# ESP32_USBC.net
KiCad netlist of a schematic drawn in Altium Designer
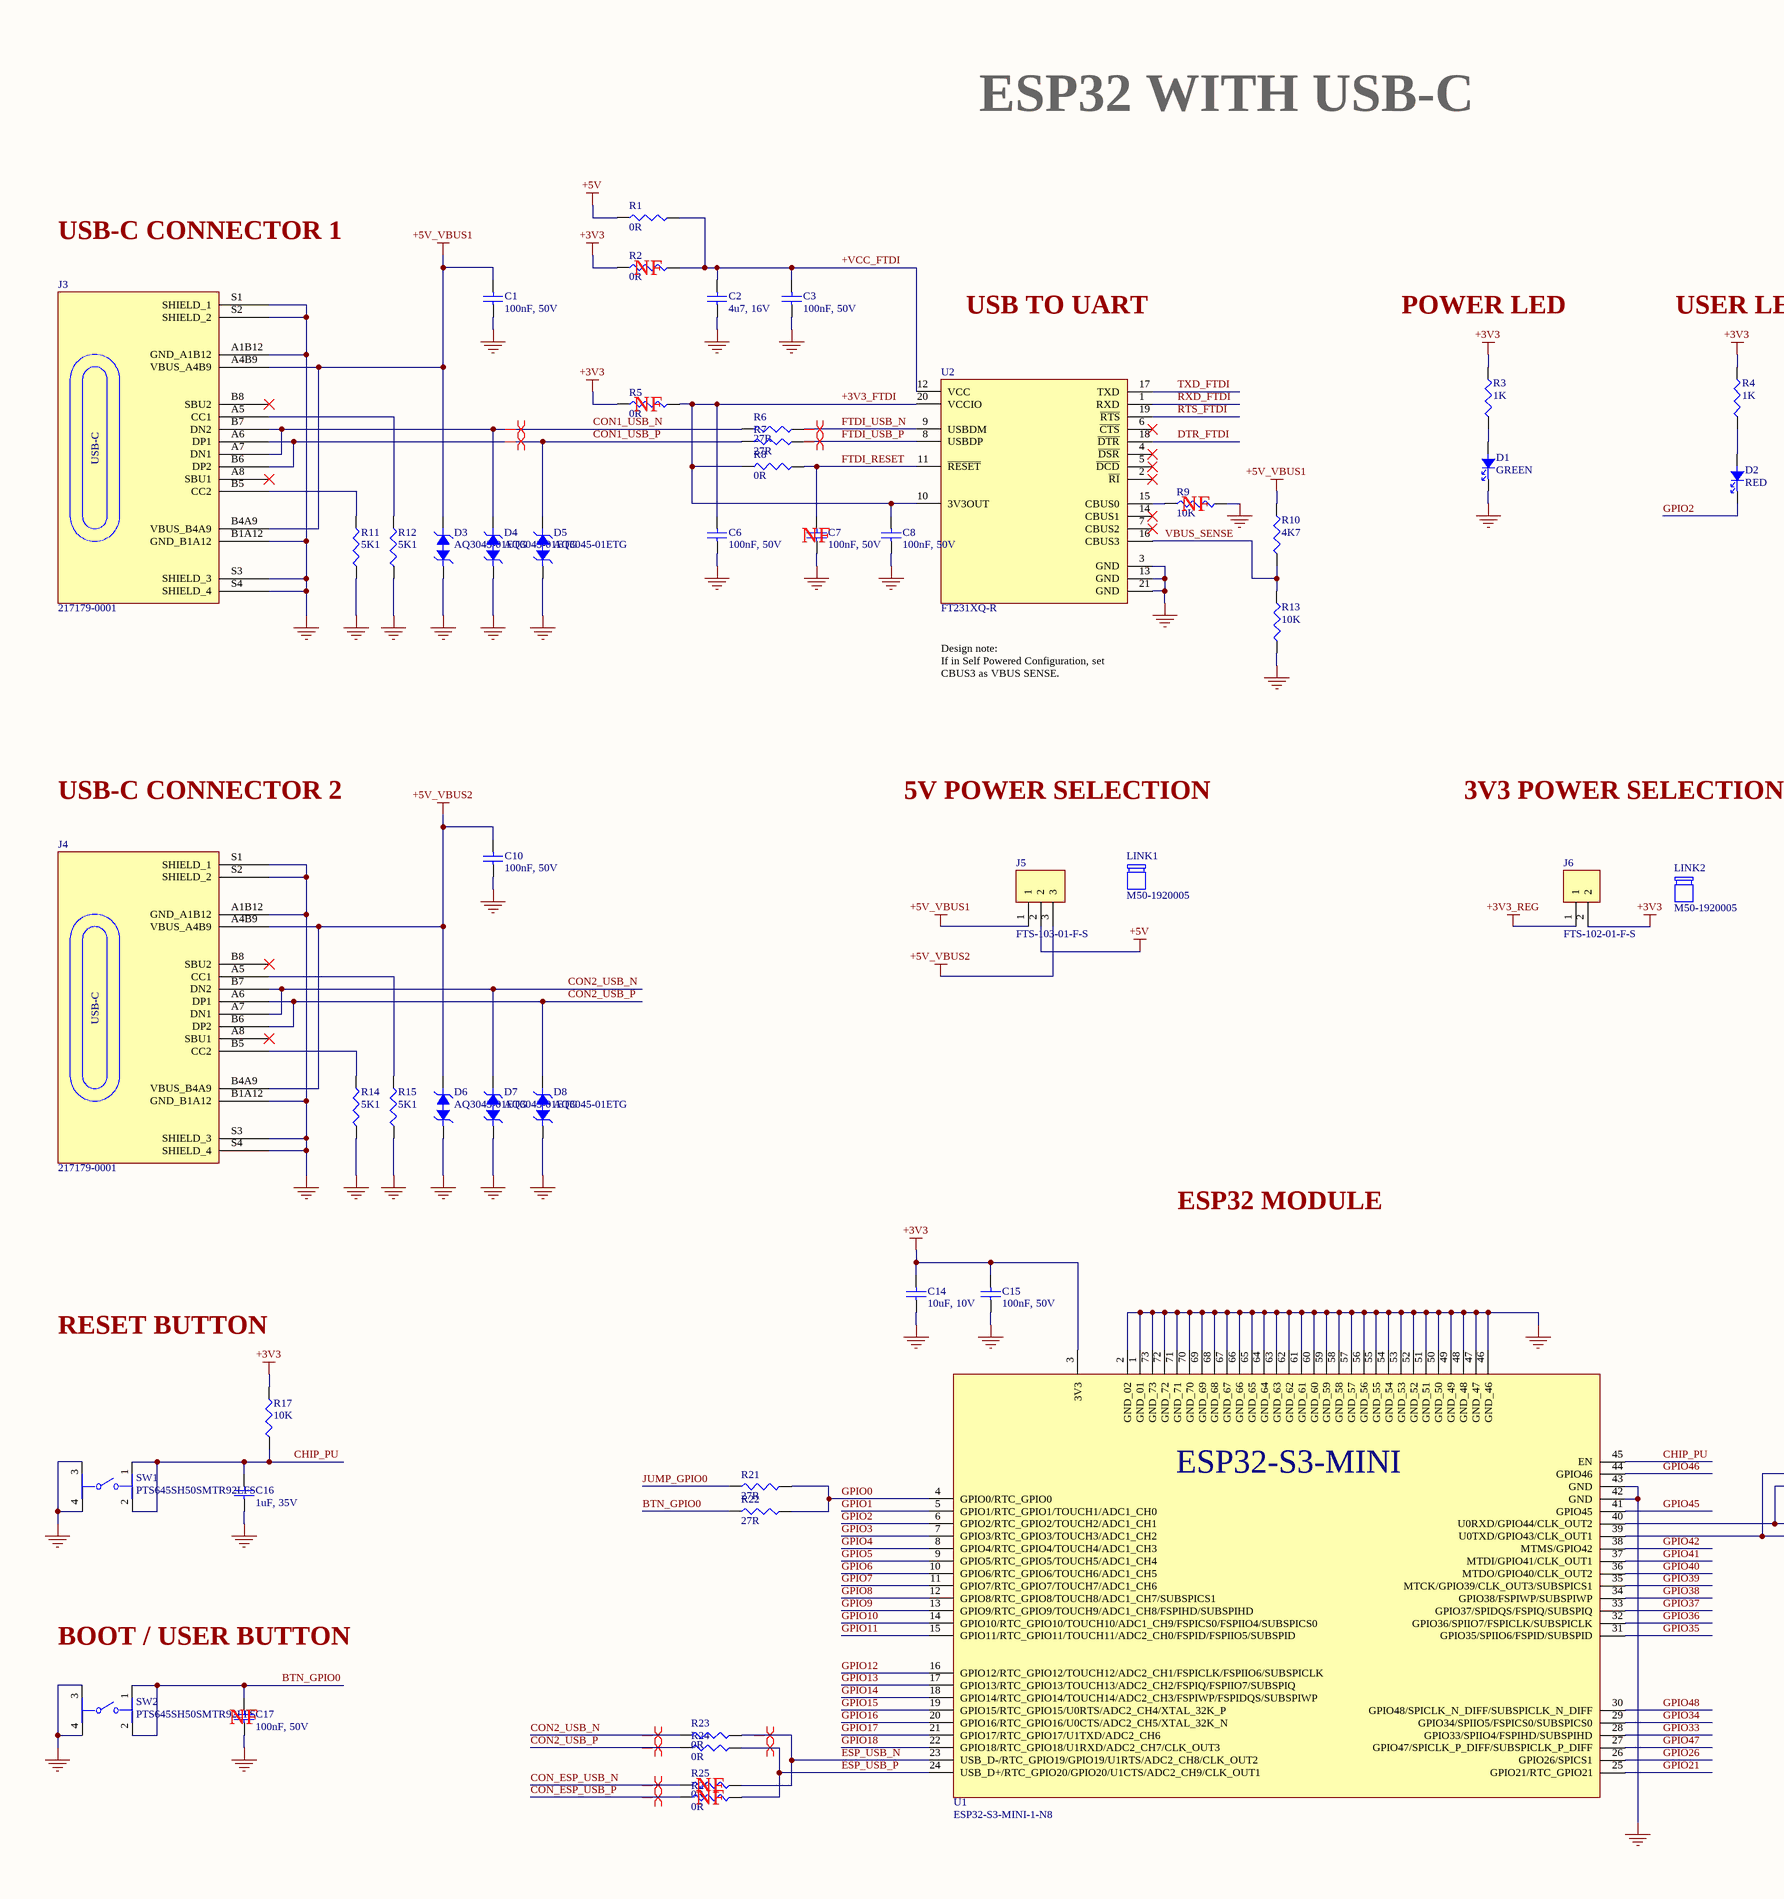
[diagram p0: ESP32_USBC.SchDoc, left]
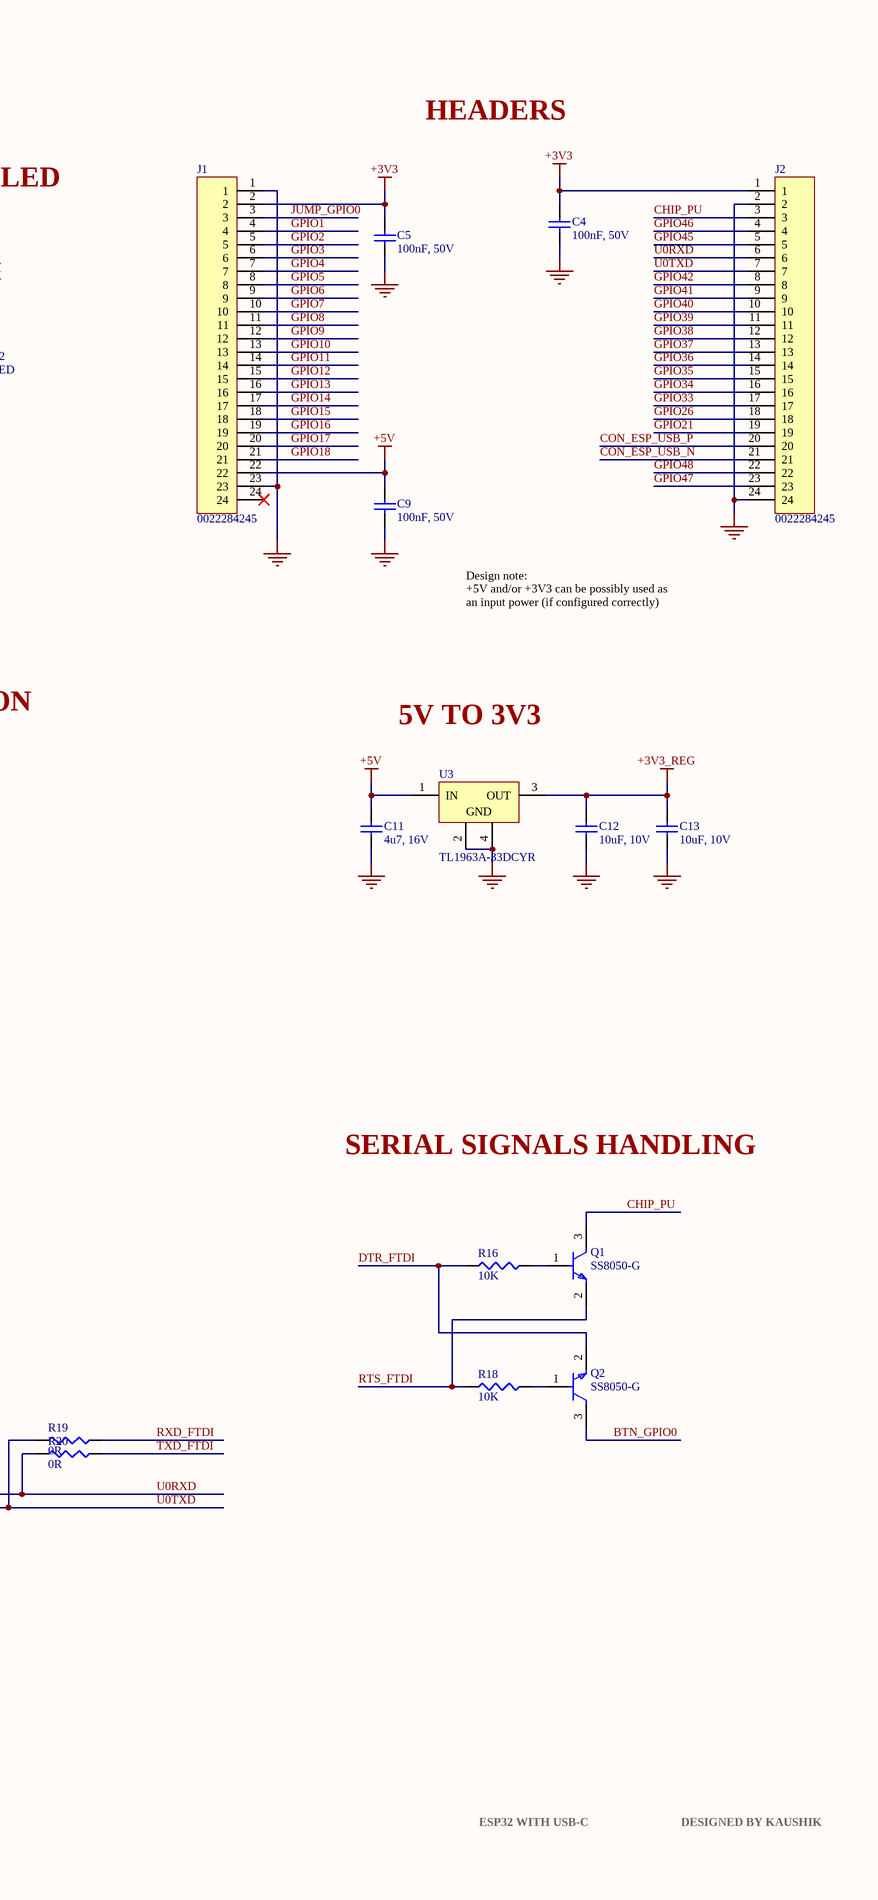
[diagram p1: ESP32_USBC.SchDoc, right]

(export (version "E")
  (design (tool "Eeschema 10.0.6"))
  (components
    (comp (ref "C1")
      (value "100nF, 50V")
      (footprint "CAPC1005X55N")
      (description "CAP CER 0.1UF 50V X7R 0402")
      (fields
        (field (name "MANUFACTURER") "Samsung")
        (field (name "MANUFACTURER PART NUMBER") "CL05B104KB54PNC")
      )
      (libsource (lib "Schlib") (part "CL05B104KB54PNC"))
    )
    (comp (ref "C2")
      (value "4u7, 16V")
      (footprint "CAPC1005X55N")
      (description "CAP CER 4.7UF 16V X5R 0402")
      (fields
        (field (name "MANUFACTURER") "Samsung")
        (field (name "MANUFACTURER PART NUMBER") "CL05A475MO5NUNC")
      )
      (libsource (lib "Schlib") (part "CL05A475MO5NUNC"))
    )
    (comp (ref "C3")
      (value "100nF, 50V")
      (footprint "CAPC1005X55N")
      (description "CAP CER 0.1UF 50V X7R 0402")
      (fields
        (field (name "MANUFACTURER") "Samsung")
        (field (name "MANUFACTURER PART NUMBER") "CL05B104KB54PNC")
      )
      (libsource (lib "Schlib") (part "CL05B104KB54PNC"))
    )
    (comp (ref "C4")
      (value "100nF, 50V")
      (footprint "CAPC1005X55N")
      (description "CAP CER 0.1UF 50V X7R 0402")
      (fields
        (field (name "MANUFACTURER") "Samsung")
        (field (name "MANUFACTURER PART NUMBER") "CL05B104KB54PNC")
      )
      (libsource (lib "Schlib") (part "CL05B104KB54PNC"))
    )
    (comp (ref "C5")
      (value "100nF, 50V")
      (footprint "CAPC1005X55N")
      (description "CAP CER 0.1UF 50V X7R 0402")
      (fields
        (field (name "MANUFACTURER") "Samsung")
        (field (name "MANUFACTURER PART NUMBER") "CL05B104KB54PNC")
      )
      (libsource (lib "Schlib") (part "CL05B104KB54PNC"))
    )
    (comp (ref "C6")
      (value "100nF, 50V")
      (footprint "CAPC1005X55N")
      (description "CAP CER 0.1UF 50V X7R 0402")
      (fields
        (field (name "MANUFACTURER") "Samsung")
        (field (name "MANUFACTURER PART NUMBER") "CL05B104KB54PNC")
      )
      (libsource (lib "Schlib") (part "CL05B104KB54PNC"))
    )
    (comp (ref "C7")
      (value "100nF, 50V")
      (footprint "CAPC1005X55N")
      (description "CAP CER 0.1UF 50V X7R 0402")
      (fields
        (field (name "MANUFACTURER") "Samsung")
        (field (name "MANUFACTURER PART NUMBER") "CL05B104KB54PNC")
      )
      (libsource (lib "Schlib") (part "CL05B104KB54PNC"))
    )
    (comp (ref "C8")
      (value "100nF, 50V")
      (footprint "CAPC1005X55N")
      (description "CAP CER 0.1UF 50V X7R 0402")
      (fields
        (field (name "MANUFACTURER") "Samsung")
        (field (name "MANUFACTURER PART NUMBER") "CL05B104KB54PNC")
      )
      (libsource (lib "Schlib") (part "CL05B104KB54PNC"))
    )
    (comp (ref "C9")
      (value "100nF, 50V")
      (footprint "CAPC1005X55N")
      (description "CAP CER 0.1UF 50V X7R 0402")
      (fields
        (field (name "MANUFACTURER") "Samsung")
        (field (name "MANUFACTURER PART NUMBER") "CL05B104KB54PNC")
      )
      (libsource (lib "Schlib") (part "CL05B104KB54PNC"))
    )
    (comp (ref "C10")
      (value "100nF, 50V")
      (footprint "CAPC1005X55N")
      (description "CAP CER 0.1UF 50V X7R 0402")
      (fields
        (field (name "MANUFACTURER") "Samsung")
        (field (name "MANUFACTURER PART NUMBER") "CL05B104KB54PNC")
      )
      (libsource (lib "Schlib") (part "CL05B104KB54PNC"))
    )
    (comp (ref "C11")
      (value "4u7, 16V")
      (footprint "CAPC1005X55N")
      (description "CAP CER 4.7UF 16V X5R 0402")
      (fields
        (field (name "MANUFACTURER") "Samsung")
        (field (name "MANUFACTURER PART NUMBER") "CL05A475MO5NUNC")
      )
      (libsource (lib "Schlib") (part "CL05A475MO5NUNC"))
    )
    (comp (ref "C12")
      (value "10uF, 10V")
      (footprint "CAPC1005X55N")
      (description "CAP CER 10UF 10V X5R 0402")
      (fields
        (field (name "MANUFACTURER") "Samsung")
        (field (name "MANUFACTURER PART NUMBER") "CL05A106MP8NUB8")
      )
      (libsource (lib "Schlib") (part "CL05A106MP8NUB8"))
    )
    (comp (ref "C13")
      (value "10uF, 10V")
      (footprint "CAPC1005X55N")
      (description "CAP CER 10UF 10V X5R 0402")
      (fields
        (field (name "MANUFACTURER") "Samsung")
        (field (name "MANUFACTURER PART NUMBER") "CL05A106MP8NUB8")
      )
      (libsource (lib "Schlib") (part "CL05A106MP8NUB8"))
    )
    (comp (ref "C14")
      (value "10uF, 10V")
      (footprint "CAPC1005X55N")
      (description "CAP CER 10UF 10V X5R 0402")
      (fields
        (field (name "MANUFACTURER") "Samsung")
        (field (name "MANUFACTURER PART NUMBER") "CL05A106MP8NUB8")
      )
      (libsource (lib "Schlib") (part "CL05A106MP8NUB8"))
    )
    (comp (ref "C15")
      (value "100nF, 50V")
      (footprint "CAPC1005X55N")
      (description "CAP CER 0.1UF 50V X7R 0402")
      (fields
        (field (name "MANUFACTURER") "Samsung")
        (field (name "MANUFACTURER PART NUMBER") "CL05B104KB54PNC")
      )
      (libsource (lib "Schlib") (part "CL05B104KB54PNC"))
    )
    (comp (ref "C16")
      (value "1uF, 35V")
      (footprint "CAPC1005X55N")
      (description "CAP CER 1UF 35V X5R 0402")
      (fields
        (field (name "MANUFACTURER") "Samsung")
        (field (name "MANUFACTURER PART NUMBER") "CL05A105KL5NRNC")
      )
      (libsource (lib "Schlib") (part "CL05A105KL5NRNC"))
    )
    (comp (ref "C17")
      (value "100nF, 50V")
      (footprint "CAPC1005X55N")
      (description "CAP CER 0.1UF 50V X7R 0402")
      (fields
        (field (name "MANUFACTURER") "Samsung")
        (field (name "MANUFACTURER PART NUMBER") "CL05B104KB54PNC")
      )
      (libsource (lib "Schlib") (part "CL05B104KB54PNC"))
    )
    (comp (ref "D1")
      (value "GREEN")
      (footprint "LED0402G")
      (description "LED YLW-GRN 0402 SMD")
      (fields
        (field (name "MANUFACTURER") "Vishay")
        (field (name "MANUFACTURER PART NUMBER") "VLMG1500-GS08")
      )
      (libsource (lib "Schlib") (part "VLMG1500-GS08"))
    )
    (comp (ref "D2")
      (value "RED")
      (footprint "LED0402R")
      (description "LED RED 0402 SMD")
      (fields
        (field (name "MANUFACTURER") "Vishay")
        (field (name "MANUFACTURER PART NUMBER") "VLMS1500-GS08")
      )
      (libsource (lib "Schlib") (part "VLMS1500-GS08"))
    )
    (comp (ref "D3")
      (value "AQ3045-01ETG")
      (footprint "SOD882")
      (description "TVS DIODE 5.3VWM 12VC SOD882")
      (fields (field (name "MANUFACTURER") "Littelfuse") (field (name "LCSC PART NUMBER") "C3710326"))
      (libsource (lib "Schlib") (part "AQ3045-01ETG"))
    )
    (comp (ref "D4")
      (value "AQ3045-01ETG")
      (footprint "SOD882")
      (description "TVS DIODE 5.3VWM 12VC SOD882")
      (fields (field (name "MANUFACTURER") "Littelfuse") (field (name "LCSC PART NUMBER") "C3710326"))
      (libsource (lib "Schlib") (part "AQ3045-01ETG"))
    )
    (comp (ref "D5")
      (value "AQ3045-01ETG")
      (footprint "SOD882")
      (description "TVS DIODE 5.3VWM 12VC SOD882")
      (fields (field (name "MANUFACTURER") "Littelfuse") (field (name "LCSC PART NUMBER") "C3710326"))
      (libsource (lib "Schlib") (part "AQ3045-01ETG"))
    )
    (comp (ref "D6")
      (value "AQ3045-01ETG")
      (footprint "SOD882")
      (description "TVS DIODE 5.3VWM 12VC SOD882")
      (fields (field (name "MANUFACTURER") "Littelfuse") (field (name "LCSC PART NUMBER") "C3710326"))
      (libsource (lib "Schlib") (part "AQ3045-01ETG"))
    )
    (comp (ref "D7")
      (value "AQ3045-01ETG")
      (footprint "SOD882")
      (description "TVS DIODE 5.3VWM 12VC SOD882")
      (fields (field (name "MANUFACTURER") "Littelfuse") (field (name "LCSC PART NUMBER") "C3710326"))
      (libsource (lib "Schlib") (part "AQ3045-01ETG"))
    )
    (comp (ref "D8")
      (value "AQ3045-01ETG")
      (footprint "SOD882")
      (description "TVS DIODE 5.3VWM 12VC SOD882")
      (fields (field (name "MANUFACTURER") "Littelfuse") (field (name "LCSC PART NUMBER") "C3710326"))
      (libsource (lib "Schlib") (part "AQ3045-01ETG"))
    )
    (comp (ref "J1")
      (value "0022284245")
      (footprint "HDR_1X24_2.54MM")
      (description "CONN HEADER VERT 24POS 2.54MM")
      (fields (field (name "MANUFACTURER") "Molex") (field (name "LCSC PART NUMBER") "C7145888"))
      (libsource (lib "Schlib") (part "0022284245"))
    )
    (comp (ref "J2")
      (value "0022284245")
      (footprint "HDR_1X24_2.54MM")
      (description "CONN HEADER VERT 24POS 2.54MM")
      (fields (field (name "MANUFACTURER") "Molex") (field (name "LCSC PART NUMBER") "C7145888"))
      (libsource (lib "") (part "0022284245_1"))
    )
    (comp (ref "J3")
      (value "217179-0001")
      (footprint "FP-2171790001-MFG")
      (description "CONN RCP USB2.0 TYP C 24P SMD RA")
      (fields (field (name "MANUFACTURER") "Molex") (field (name "LCSC PART NUMBER") "C3197684"))
      (libsource (lib "Schlib") (part "217179-0001"))
    )
    (comp (ref "J4")
      (value "217179-0001")
      (footprint "FP-2171790001-MFG")
      (description "CONN RCP USB2.0 TYP C 24P SMD RA")
      (fields (field (name "MANUFACTURER") "Molex") (field (name "LCSC PART NUMBER") "C3197684"))
      (libsource (lib "Schlib") (part "217179-0001"))
    )
    (comp (ref "J5")
      (value "FTS-103-01-F-S")
      (footprint "HDR_1X3_1.27MM")
      (description "CONN HEADER VERT 3POS 1.27MM")
      (fields (field (name "MANUFACTURER") "Samtec") (field (name "LCSC PART NUMBER") "C3333578"))
      (libsource (lib "Schlib") (part "FTS-103-01-F-S"))
    )
    (comp (ref "J6")
      (value "FTS-102-01-F-S")
      (footprint "HDR_1X2_1.27MM")
      (description "CONN HEADER VERT 2POS 1.27MM")
      (fields (field (name "MANUFACTURER") "Samtec") (field (name "LCSC PART NUMBER") "C6045317"))
      (libsource (lib "Schlib") (part "FTS-102-01-F-S"))
    )
    (comp (ref "LINK1")
      (value "M50-1920005")
      (description "CONN SHUNT 1.27MM RED")
      (fields (field (name "MANUFACTURER") "Harwin") (field (name "LCSC PART NUMBER") "C6985646"))
      (libsource (lib "Schlib") (part "M50-1920005"))
    )
    (comp (ref "LINK2")
      (value "M50-1920005")
      (description "CONN SHUNT 1.27MM RED")
      (fields (field (name "MANUFACTURER") "Harwin") (field (name "LCSC PART NUMBER") "C6985646"))
      (libsource (lib "Schlib") (part "M50-1920005"))
    )
    (comp (ref "Q1")
      (value "SS8050-G")
      (footprint "FP-SS8050-G-IPC_B")
      (description "TRANS NPN 25V 1.5A SOT23-3")
      (fields (field (name "MANUFACTURER") "Comchip") (field (name "LCSC PART NUMBER") "C164886"))
      (libsource (lib "Schlib") (part "SS8050-G"))
    )
    (comp (ref "Q2")
      (value "SS8050-G")
      (footprint "FP-SS8050-G-IPC_B")
      (description "TRANS NPN 25V 1.5A SOT23-3")
      (fields (field (name "MANUFACTURER") "Comchip") (field (name "LCSC PART NUMBER") "C164886"))
      (libsource (lib "Schlib") (part "SS8050-G"))
    )
    (comp (ref "R1")
      (value "0R")
      (footprint "RESC1005X37N")
      (description "RES 0 OHM JUMPER 1/16W 0402")
      (fields
        (field (name "MANUFACTURER") "Yageo")
        (field (name "MANUFACTURER PART NUMBER") "RC0402JR-070RL")
      )
      (libsource (lib "Schlib") (part "RC0402JR-070RL"))
    )
    (comp (ref "R2")
      (value "0R")
      (footprint "RESC1005X37N")
      (description "RES 0 OHM JUMPER 1/16W 0402")
      (fields
        (field (name "MANUFACTURER") "Yageo")
        (field (name "MANUFACTURER PART NUMBER") "RC0402JR-070RL")
      )
      (libsource (lib "Schlib") (part "RC0402JR-070RL"))
    )
    (comp (ref "R3")
      (value "1K")
      (footprint "RESC1005X37N")
      (description "RES 1K OHM 1% 1/16W 0402")
      (fields
        (field (name "MANUFACTURER") "Yageo")
        (field (name "MANUFACTURER PART NUMBER") "RC0402FR-071KL")
      )
      (libsource (lib "Schlib") (part "RC0402FR-071KL"))
    )
    (comp (ref "R4")
      (value "1K")
      (footprint "RESC1005X37N")
      (description "RES 1K OHM 1% 1/16W 0402")
      (fields
        (field (name "MANUFACTURER") "Yageo")
        (field (name "MANUFACTURER PART NUMBER") "RC0402FR-071KL")
      )
      (libsource (lib "Schlib") (part "RC0402FR-071KL"))
    )
    (comp (ref "R5")
      (value "0R")
      (footprint "RESC1005X37N")
      (description "RES 0 OHM JUMPER 1/16W 0402")
      (fields
        (field (name "MANUFACTURER") "Yageo")
        (field (name "MANUFACTURER PART NUMBER") "RC0402JR-070RL")
      )
      (libsource (lib "Schlib") (part "RC0402JR-070RL"))
    )
    (comp (ref "R6")
      (value "27R")
      (footprint "RESC1005X37N")
      (description "RES 27 OHM 1% 1/16W 0402")
      (fields
        (field (name "MANUFACTURER") "Yageo")
        (field (name "MANUFACTURER PART NUMBER") "RC0402FR-0727RL")
      )
      (libsource (lib "Schlib") (part "RC0402FR-0727RL"))
    )
    (comp (ref "R7")
      (value "27R")
      (footprint "RESC1005X37N")
      (description "RES 27 OHM 1% 1/16W 0402")
      (fields
        (field (name "MANUFACTURER") "Yageo")
        (field (name "MANUFACTURER PART NUMBER") "RC0402FR-0727RL")
      )
      (libsource (lib "Schlib") (part "RC0402FR-0727RL"))
    )
    (comp (ref "R8")
      (value "0R")
      (footprint "RESC1005X37N")
      (description "RES 0 OHM JUMPER 1/16W 0402")
      (fields
        (field (name "MANUFACTURER") "Yageo")
        (field (name "MANUFACTURER PART NUMBER") "RC0402JR-070RL")
      )
      (libsource (lib "Schlib") (part "RC0402JR-070RL"))
    )
    (comp (ref "R9")
      (value "10K")
      (footprint "RESC1005X37N")
      (description "RES SMD 10K OHM 1% 1/16W 0402")
      (fields
        (field (name "MANUFACTURER") "Yageo")
        (field (name "MANUFACTURER PART NUMBER") "AC0402FR-0710KL")
      )
      (libsource (lib "Schlib") (part "AC0402FR-0710KL"))
    )
    (comp (ref "R10")
      (value "4K7")
      (footprint "RESC1005X37N")
      (description "RES 4.7K OHM 1% 1/16W 0402")
      (fields
        (field (name "MANUFACTURER") "Yageo")
        (field (name "MANUFACTURER PART NUMBER") "RC0402FR-074K7L")
      )
      (libsource (lib "Schlib") (part "RC0402FR-074K7L"))
    )
    (comp (ref "R11")
      (value "5K1")
      (footprint "RESC1005X37N")
      (description "RES SMD 5.1K OHM 1% 1/16W 0402")
      (fields
        (field (name "MANUFACTURER") "Yageo")
        (field (name "MANUFACTURER PART NUMBER") "AC0402FR-075K1L")
      )
      (libsource (lib "Schlib") (part "AC0402FR-075K1L"))
    )
    (comp (ref "R12")
      (value "5K1")
      (footprint "RESC1005X37N")
      (description "RES SMD 5.1K OHM 1% 1/16W 0402")
      (fields
        (field (name "MANUFACTURER") "Yageo")
        (field (name "MANUFACTURER PART NUMBER") "AC0402FR-075K1L")
      )
      (libsource (lib "Schlib") (part "AC0402FR-075K1L"))
    )
    (comp (ref "R13")
      (value "10K")
      (footprint "RESC1005X37N")
      (description "RES SMD 10K OHM 1% 1/16W 0402")
      (fields
        (field (name "MANUFACTURER") "Yageo")
        (field (name "MANUFACTURER PART NUMBER") "AC0402FR-0710KL")
      )
      (libsource (lib "Schlib") (part "AC0402FR-0710KL"))
    )
    (comp (ref "R14")
      (value "5K1")
      (footprint "RESC1005X37N")
      (description "RES SMD 5.1K OHM 1% 1/16W 0402")
      (fields
        (field (name "MANUFACTURER") "Yageo")
        (field (name "MANUFACTURER PART NUMBER") "AC0402FR-075K1L")
      )
      (libsource (lib "Schlib") (part "AC0402FR-075K1L"))
    )
    (comp (ref "R15")
      (value "5K1")
      (footprint "RESC1005X37N")
      (description "RES SMD 5.1K OHM 1% 1/16W 0402")
      (fields
        (field (name "MANUFACTURER") "Yageo")
        (field (name "MANUFACTURER PART NUMBER") "AC0402FR-075K1L")
      )
      (libsource (lib "Schlib") (part "AC0402FR-075K1L"))
    )
    (comp (ref "R16")
      (value "10K")
      (footprint "RESC1005X37N")
      (description "RES SMD 10K OHM 1% 1/16W 0402")
      (fields
        (field (name "MANUFACTURER") "Yageo")
        (field (name "MANUFACTURER PART NUMBER") "AC0402FR-0710KL")
      )
      (libsource (lib "Schlib") (part "AC0402FR-0710KL"))
    )
    (comp (ref "R17")
      (value "10K")
      (footprint "RESC1005X37N")
      (description "RES SMD 10K OHM 1% 1/16W 0402")
      (fields
        (field (name "MANUFACTURER") "Yageo")
        (field (name "MANUFACTURER PART NUMBER") "AC0402FR-0710KL")
      )
      (libsource (lib "Schlib") (part "AC0402FR-0710KL"))
    )
    (comp (ref "R18")
      (value "10K")
      (footprint "RESC1005X37N")
      (description "RES SMD 10K OHM 1% 1/16W 0402")
      (fields
        (field (name "MANUFACTURER") "Yageo")
        (field (name "MANUFACTURER PART NUMBER") "AC0402FR-0710KL")
      )
      (libsource (lib "Schlib") (part "AC0402FR-0710KL"))
    )
    (comp (ref "R19")
      (value "0R")
      (footprint "RESC1005X37N")
      (description "RES 0 OHM JUMPER 1/16W 0402")
      (fields
        (field (name "MANUFACTURER") "Yageo")
        (field (name "MANUFACTURER PART NUMBER") "RC0402JR-070RL")
      )
      (libsource (lib "Schlib") (part "RC0402JR-070RL"))
    )
    (comp (ref "R20")
      (value "0R")
      (footprint "RESC1005X37N")
      (description "RES 0 OHM JUMPER 1/16W 0402")
      (fields
        (field (name "MANUFACTURER") "Yageo")
        (field (name "MANUFACTURER PART NUMBER") "RC0402JR-070RL")
      )
      (libsource (lib "Schlib") (part "RC0402JR-070RL"))
    )
    (comp (ref "R21")
      (value "27R")
      (footprint "RESC1005X37N")
      (description "RES 27 OHM 1% 1/16W 0402")
      (fields
        (field (name "MANUFACTURER") "Yageo")
        (field (name "MANUFACTURER PART NUMBER") "RC0402FR-0727RL")
      )
      (libsource (lib "Schlib") (part "RC0402FR-0727RL"))
    )
    (comp (ref "R22")
      (value "27R")
      (footprint "RESC1005X37N")
      (description "RES 27 OHM 1% 1/16W 0402")
      (fields
        (field (name "MANUFACTURER") "Yageo")
        (field (name "MANUFACTURER PART NUMBER") "RC0402FR-0727RL")
      )
      (libsource (lib "Schlib") (part "RC0402FR-0727RL"))
    )
    (comp (ref "R23")
      (value "0R")
      (footprint "RESC1005X37N")
      (description "RES 0 OHM JUMPER 1/16W 0402")
      (fields
        (field (name "MANUFACTURER") "Yageo")
        (field (name "MANUFACTURER PART NUMBER") "RC0402JR-070RL")
      )
      (libsource (lib "Schlib") (part "RC0402JR-070RL"))
    )
    (comp (ref "R24")
      (value "0R")
      (footprint "RESC1005X37N")
      (description "RES 0 OHM JUMPER 1/16W 0402")
      (fields
        (field (name "MANUFACTURER") "Yageo")
        (field (name "MANUFACTURER PART NUMBER") "RC0402JR-070RL")
      )
      (libsource (lib "Schlib") (part "RC0402JR-070RL"))
    )
    (comp (ref "R25")
      (value "0R")
      (footprint "RESC1005X37N")
      (description "RES 0 OHM JUMPER 1/16W 0402")
      (fields
        (field (name "MANUFACTURER") "Yageo")
        (field (name "MANUFACTURER PART NUMBER") "RC0402JR-070RL")
      )
      (libsource (lib "Schlib") (part "RC0402JR-070RL"))
    )
    (comp (ref "R26")
      (value "0R")
      (footprint "RESC1005X37N")
      (description "RES 0 OHM JUMPER 1/16W 0402")
      (fields
        (field (name "MANUFACTURER") "Yageo")
        (field (name "MANUFACTURER PART NUMBER") "RC0402JR-070RL")
      )
      (libsource (lib "Schlib") (part "RC0402JR-070RL"))
    )
    (comp (ref "SW1")
      (value "PTS645SH50SMTR92LFS")
      (footprint "FP-PTS645SH50SMTR92LFS-MFG")
      (description "SWITCH TACTILE SPST-NO 0.05A 12V")
      (fields (field (name "MANUFACTURER") "ITT C&K") (field (name "LCSC PART NUMBER") "C221869"))
      (libsource (lib "Schlib") (part "PTS645SH50SMTR92LFS"))
    )
    (comp (ref "SW2")
      (value "PTS645SH50SMTR92LFS")
      (footprint "FP-PTS645SH50SMTR92LFS-MFG")
      (description "SWITCH TACTILE SPST-NO 0.05A 12V")
      (fields (field (name "MANUFACTURER") "ITT C&K") (field (name "LCSC PART NUMBER") "C221869"))
      (libsource (lib "Schlib") (part "PTS645SH50SMTR92LFS"))
    )
    (comp (ref "U1")
      (value "ESP32-S3-MINI-1-N8")
      (footprint "XCVR_ESP32-S3-MINI-1-N8")
      (description "SMD Module, ESP32-S3FN8, 8 mb Sp")
      (fields (field (name "MANUFACTURER") "Espressif Systems") (field (name "LCSC PART NUMBER") "C2913206"))
      (libsource (lib "Schlib") (part "ESP32-S3-MINI-1-N8"))
    )
    (comp (ref "U2")
      (value "FT231XQ-R")
      (footprint "FP-QFN-20-IPC_B")
      (description "IC USB SERIAL FULL UART 20QFN")
      (fields (field (name "MANUFACTURER") "FTDI") (field (name "LCSC PART NUMBER") "C132159"))
      (libsource (lib "Schlib") (part "FT231XQ-R"))
    )
    (comp (ref "U3")
      (value "TL1963A-33DCYR")
      (footprint "DCY0004A_N")
      (description "IC REG LINEAR 3.3V 1.5A SOT223-4")
      (fields (field (name "MANUFACTURER") "Texas Instruments") (field (name "LCSC PART NUMBER") "C181262"))
      (libsource (lib "Schlib") (part "TL1963A-33DCYR"))
    )
  )
  (nets
    (net (code "1") (name "+3V3") (class "Default")
      (node (ref "C14") (pin "2") (pinfunction "2_2") (pintype "passive"))
      (node (ref "C15") (pin "2") (pinfunction "2_2") (pintype "passive"))
      (node (ref "C4") (pin "2") (pinfunction "2_2") (pintype "passive"))
      (node (ref "C5") (pin "2") (pinfunction "2_2") (pintype "passive"))
      (node (ref "J1") (pin "2") (pinfunction "2_2") (pintype "passive"))
      (node (ref "J2") (pin "1") (pinfunction "1_1") (pintype "passive"))
      (node (ref "J6") (pin "2") (pinfunction "2_2") (pintype "passive"))
      (node (ref "R17") (pin "2") (pinfunction "2_2") (pintype "passive"))
      (node (ref "R2") (pin "1") (pinfunction "1_1") (pintype "passive"))
      (node (ref "R3") (pin "2") (pinfunction "2_2") (pintype "passive"))
      (node (ref "R4") (pin "2") (pinfunction "2_2") (pintype "passive"))
      (node (ref "R5") (pin "1") (pinfunction "1_1") (pintype "passive"))
      (node (ref "U1") (pin "3") (pinfunction "3V3_3") (pintype "passive"))
    )
    (net (code "2") (name "+3V3_REG") (class "Default")
      (node (ref "C12") (pin "2") (pinfunction "2_2") (pintype "passive"))
      (node (ref "C13") (pin "2") (pinfunction "2_2") (pintype "passive"))
      (node (ref "J6") (pin "1") (pinfunction "1_1") (pintype "passive"))
      (node (ref "U3") (pin "3") (pinfunction "OUT_3") (pintype "power_in"))
    )
    (net (code "3") (name "+5V") (class "Default")
      (node (ref "C11") (pin "2") (pinfunction "2_2") (pintype "passive"))
      (node (ref "C9") (pin "2") (pinfunction "2_2") (pintype "passive"))
      (node (ref "J1") (pin "22") (pinfunction "22_22") (pintype "passive"))
      (node (ref "J5") (pin "2") (pinfunction "2_2") (pintype "passive"))
      (node (ref "R1") (pin "1") (pinfunction "1_1") (pintype "passive"))
      (node (ref "U3") (pin "1") (pinfunction "IN_1") (pintype "power_in"))
    )
    (net (code "4") (name "+5V_VBUS1") (class "Default")
      (node (ref "C1") (pin "2") (pinfunction "2_2") (pintype "passive"))
      (node (ref "D3") (pin "2") (pinfunction "2_2") (pintype "passive"))
      (node (ref "J3") (pin "A4B9") (pinfunction "VBUS_A4B9_A4B9") (pintype "passive"))
      (node (ref "J3") (pin "B4A9") (pinfunction "VBUS_B4A9_B4A9") (pintype "passive"))
      (node (ref "J5") (pin "1") (pinfunction "1_1") (pintype "passive"))
      (node (ref "R10") (pin "2") (pinfunction "2_2") (pintype "passive"))
    )
    (net (code "5") (name "+5V_VBUS2") (class "Default")
      (node (ref "C10") (pin "2") (pinfunction "2_2") (pintype "passive"))
      (node (ref "D6") (pin "2") (pinfunction "2_2") (pintype "passive"))
      (node (ref "J4") (pin "A4B9") (pinfunction "VBUS_A4B9_A4B9") (pintype "passive"))
      (node (ref "J4") (pin "B4A9") (pinfunction "VBUS_B4A9_B4A9") (pintype "passive"))
      (node (ref "J5") (pin "3") (pinfunction "3_3") (pintype "passive"))
    )
    (net (code "6") (name "/+3V3_FTDI") (class "Default")
      (node (ref "C6") (pin "2") (pinfunction "2_2") (pintype "passive"))
      (node (ref "C8") (pin "2") (pinfunction "2_2") (pintype "passive"))
      (node (ref "R5") (pin "2") (pinfunction "2_2") (pintype "passive"))
      (node (ref "R8") (pin "1") (pinfunction "1_1") (pintype "passive"))
      (node (ref "U2") (pin "10") (pinfunction "3V3OUT_10") (pintype "passive"))
      (node (ref "U2") (pin "20") (pinfunction "VCCIO_20") (pintype "passive"))
    )
    (net (code "7") (name "/+VCC_FTDI") (class "Default")
      (node (ref "C2") (pin "2") (pinfunction "2_2") (pintype "passive"))
      (node (ref "C3") (pin "2") (pinfunction "2_2") (pintype "passive"))
      (node (ref "R1") (pin "2") (pinfunction "2_2") (pintype "passive"))
      (node (ref "R2") (pin "2") (pinfunction "2_2") (pintype "passive"))
      (node (ref "U2") (pin "12") (pinfunction "VCC_12") (pintype "passive"))
    )
    (net (code "8") (name "/BTN_GPIO0") (class "Default")
      (node (ref "C17") (pin "2") (pinfunction "2_2") (pintype "passive"))
      (node (ref "Q2") (pin "3") (pinfunction "C_3") (pintype "passive"))
      (node (ref "R22") (pin "1") (pinfunction "1_1") (pintype "passive"))
      (node (ref "SW2") (pin "1") (pinfunction "1_1") (pintype "passive"))
      (node (ref "SW2") (pin "2") (pinfunction "2_2") (pintype "passive"))
    )
    (net (code "9") (name "/CHIP_PU") (class "Default")
      (node (ref "C16") (pin "2") (pinfunction "2_2") (pintype "passive"))
      (node (ref "J2") (pin "3") (pinfunction "3_3") (pintype "passive"))
      (node (ref "Q1") (pin "3") (pinfunction "C_3") (pintype "passive"))
      (node (ref "R17") (pin "1") (pinfunction "1_1") (pintype "passive"))
      (node (ref "SW1") (pin "1") (pinfunction "1_1") (pintype "passive"))
      (node (ref "SW1") (pin "2") (pinfunction "2_2") (pintype "passive"))
      (node (ref "U1") (pin "45") (pinfunction "EN_45") (pintype "passive"))
    )
    (net (code "10") (name "/CON1_USB_N") (class "Default")
      (node (ref "D4") (pin "2") (pinfunction "2_2") (pintype "passive"))
      (node (ref "J3") (pin "A7") (pinfunction "DN1_A7") (pintype "passive"))
      (node (ref "J3") (pin "B7") (pinfunction "DN2_B7") (pintype "passive"))
      (node (ref "R6") (pin "1") (pinfunction "1_1") (pintype "passive"))
    )
    (net (code "11") (name "/CON1_USB_P") (class "Default")
      (node (ref "D5") (pin "2") (pinfunction "2_2") (pintype "passive"))
      (node (ref "J3") (pin "A6") (pinfunction "DP1_A6") (pintype "passive"))
      (node (ref "J3") (pin "B6") (pinfunction "DP2_B6") (pintype "passive"))
      (node (ref "R7") (pin "1") (pinfunction "1_1") (pintype "passive"))
    )
    (net (code "12") (name "/CON2_USB_N") (class "Default")
      (node (ref "D7") (pin "2") (pinfunction "2_2") (pintype "passive"))
      (node (ref "J4") (pin "A7") (pinfunction "DN1_A7") (pintype "passive"))
      (node (ref "J4") (pin "B7") (pinfunction "DN2_B7") (pintype "passive"))
      (node (ref "R23") (pin "1") (pinfunction "1_1") (pintype "passive"))
    )
    (net (code "13") (name "/CON2_USB_P") (class "Default")
      (node (ref "D8") (pin "2") (pinfunction "2_2") (pintype "passive"))
      (node (ref "J4") (pin "A6") (pinfunction "DP1_A6") (pintype "passive"))
      (node (ref "J4") (pin "B6") (pinfunction "DP2_B6") (pintype "passive"))
      (node (ref "R24") (pin "1") (pinfunction "1_1") (pintype "passive"))
    )
    (net (code "14") (name "/CON_ESP_USB_N") (class "Default")
      (node (ref "J2") (pin "21") (pinfunction "21_21") (pintype "passive"))
      (node (ref "R25") (pin "1") (pinfunction "1_1") (pintype "passive"))
    )
    (net (code "15") (name "/CON_ESP_USB_P") (class "Default")
      (node (ref "J2") (pin "20") (pinfunction "20_20") (pintype "passive"))
      (node (ref "R26") (pin "1") (pinfunction "1_1") (pintype "passive"))
    )
    (net (code "16") (name "/DTR_FTDI") (class "Default")
      (node (ref "Q2") (pin "2") (pinfunction "E_2") (pintype "passive"))
      (node (ref "R16") (pin "1") (pinfunction "1_1") (pintype "passive"))
      (node (ref "U2") (pin "18") (pinfunction "~{DTR}_18") (pintype "passive"))
    )
    (net (code "17") (name "/ESP_USB_N") (class "Default")
      (node (ref "R23") (pin "2") (pinfunction "2_2") (pintype "passive"))
      (node (ref "R25") (pin "2") (pinfunction "2_2") (pintype "passive"))
      (node (ref "U1") (pin "23") (pinfunction "USB_D-/RTC_GPIO19/GPIO19/U1RTS/ADC2_CH8/CLK_OUT2_23") (pintype "passive"))
    )
    (net (code "18") (name "/ESP_USB_P") (class "Default")
      (node (ref "R24") (pin "2") (pinfunction "2_2") (pintype "passive"))
      (node (ref "R26") (pin "2") (pinfunction "2_2") (pintype "passive"))
      (node (ref "U1") (pin "24") (pinfunction "USB_D+/RTC_GPIO20/GPIO20/U1CTS/ADC2_CH9/CLK_OUT1_24") (pintype "passive"))
    )
    (net (code "19") (name "/FTDI_RESET") (class "Default")
      (node (ref "C7") (pin "2") (pinfunction "2_2") (pintype "passive"))
      (node (ref "R8") (pin "2") (pinfunction "2_2") (pintype "passive"))
      (node (ref "U2") (pin "11") (pinfunction "~{RESET}_11") (pintype "passive"))
    )
    (net (code "20") (name "/FTDI_USB_N") (class "Default")
      (node (ref "R6") (pin "2") (pinfunction "2_2") (pintype "passive"))
      (node (ref "U2") (pin "9") (pinfunction "USBDM_9") (pintype "passive"))
    )
    (net (code "21") (name "/FTDI_USB_P") (class "Default")
      (node (ref "R7") (pin "2") (pinfunction "2_2") (pintype "passive"))
      (node (ref "U2") (pin "8") (pinfunction "USBDP_8") (pintype "passive"))
    )
    (net (code "22") (name "/GPIO0") (class "Default")
      (node (ref "R21") (pin "2") (pinfunction "2_2") (pintype "passive"))
      (node (ref "R22") (pin "2") (pinfunction "2_2") (pintype "passive"))
      (node (ref "U1") (pin "4") (pinfunction "GPIO0/RTC_GPIO0_4") (pintype "passive"))
    )
    (net (code "23") (name "/GPIO1") (class "Default")
      (node (ref "J1") (pin "4") (pinfunction "4_4") (pintype "passive"))
      (node (ref "U1") (pin "5") (pinfunction "GPIO1/RTC_GPIO1/TOUCH1/ADC1_CH0_5") (pintype "passive"))
    )
    (net (code "24") (name "/GPIO2") (class "Default")
      (node (ref "D2") (pin "1") (pinfunction "1_1") (pintype "passive"))
      (node (ref "J1") (pin "5") (pinfunction "5_5") (pintype "passive"))
      (node (ref "U1") (pin "6") (pinfunction "GPIO2/RTC_GPIO2/TOUCH2/ADC1_CH1_6") (pintype "passive"))
    )
    (net (code "25") (name "/GPIO3") (class "Default")
      (node (ref "J1") (pin "6") (pinfunction "6_6") (pintype "passive"))
      (node (ref "U1") (pin "7") (pinfunction "GPIO3/RTC_GPIO3/TOUCH3/ADC1_CH2_7") (pintype "passive"))
    )
    (net (code "26") (name "/GPIO4") (class "Default")
      (node (ref "J1") (pin "7") (pinfunction "7_7") (pintype "passive"))
      (node (ref "U1") (pin "8") (pinfunction "GPIO4/RTC_GPIO4/TOUCH4/ADC1_CH3_8") (pintype "passive"))
    )
    (net (code "27") (name "/GPIO5") (class "Default")
      (node (ref "J1") (pin "8") (pinfunction "8_8") (pintype "passive"))
      (node (ref "U1") (pin "9") (pinfunction "GPIO5/RTC_GPIO5/TOUCH5/ADC1_CH4_9") (pintype "passive"))
    )
    (net (code "28") (name "/GPIO6") (class "Default")
      (node (ref "J1") (pin "9") (pinfunction "9_9") (pintype "passive"))
      (node (ref "U1") (pin "10") (pinfunction "GPIO6/RTC_GPIO6/TOUCH6/ADC1_CH5_10") (pintype "passive"))
    )
    (net (code "29") (name "/GPIO7") (class "Default")
      (node (ref "J1") (pin "10") (pinfunction "10_10") (pintype "passive"))
      (node (ref "U1") (pin "11") (pinfunction "GPIO7/RTC_GPIO7/TOUCH7/ADC1_CH6_11") (pintype "passive"))
    )
    (net (code "30") (name "/GPIO8") (class "Default")
      (node (ref "J1") (pin "11") (pinfunction "11_11") (pintype "passive"))
      (node (ref "U1") (pin "12") (pinfunction "GPIO8/RTC_GPIO8/TOUCH8/ADC1_CH7/SUBSPICS1_12") (pintype "passive"))
    )
    (net (code "31") (name "/GPIO9") (class "Default")
      (node (ref "J1") (pin "12") (pinfunction "12_12") (pintype "passive"))
      (node (ref "U1") (pin "13") (pinfunction "GPIO9/RTC_GPIO9/TOUCH9/ADC1_CH8/FSPIHD/SUBSPIHD_13") (pintype "passive"))
    )
    (net (code "32") (name "/GPIO10") (class "Default")
      (node (ref "J1") (pin "13") (pinfunction "13_13") (pintype "passive"))
      (node (ref "U1") (pin "14") (pinfunction "GPIO10/RTC_GPIO10/TOUCH10/ADC1_CH9/FSPICS0/FSPIIO4/SUBSPICS0_14") (pintype "passive"))
    )
    (net (code "33") (name "/GPIO11") (class "Default")
      (node (ref "J1") (pin "14") (pinfunction "14_14") (pintype "passive"))
      (node (ref "U1") (pin "15") (pinfunction "GPIO11/RTC_GPIO11/TOUCH11/ADC2_CH0/FSPID/FSPIIO5/SUBSPID_15") (pintype "passive"))
    )
    (net (code "34") (name "/GPIO12") (class "Default")
      (node (ref "J1") (pin "15") (pinfunction "15_15") (pintype "passive"))
      (node (ref "U1") (pin "16") (pinfunction "GPIO12/RTC_GPIO12/TOUCH12/ADC2_CH1/FSPICLK/FSPIIO6/SUBSPICLK_16") (pintype "passive"))
    )
    (net (code "35") (name "/GPIO13") (class "Default")
      (node (ref "J1") (pin "16") (pinfunction "16_16") (pintype "passive"))
      (node (ref "U1") (pin "17") (pinfunction "GPIO13/RTC_GPIO13/TOUCH13/ADC2_CH2/FSPIQ/FSPIIO7/SUBSPIQ_17") (pintype "passive"))
    )
    (net (code "36") (name "/GPIO14") (class "Default")
      (node (ref "J1") (pin "17") (pinfunction "17_17") (pintype "passive"))
      (node (ref "U1") (pin "18") (pinfunction "GPIO14/RTC_GPIO14/TOUCH14/ADC2_CH3/FSPIWP/FSPIDQS/SUBSPIWP_18") (pintype "passive"))
    )
    (net (code "37") (name "/GPIO15") (class "Default")
      (node (ref "J1") (pin "18") (pinfunction "18_18") (pintype "passive"))
      (node (ref "U1") (pin "19") (pinfunction "GPIO15/RTC_GPIO15/U0RTS/ADC2_CH4/XTAL_32K_P_19") (pintype "passive"))
    )
    (net (code "38") (name "/GPIO16") (class "Default")
      (node (ref "J1") (pin "19") (pinfunction "19_19") (pintype "passive"))
      (node (ref "U1") (pin "20") (pinfunction "GPIO16/RTC_GPIO16/U0CTS/ADC2_CH5/XTAL_32K_N_20") (pintype "passive"))
    )
    (net (code "39") (name "/GPIO17") (class "Default")
      (node (ref "J1") (pin "20") (pinfunction "20_20") (pintype "passive"))
      (node (ref "U1") (pin "21") (pinfunction "GPIO17/RTC_GPIO17/U1TXD/ADC2_CH6_21") (pintype "passive"))
    )
    (net (code "40") (name "/GPIO18") (class "Default")
      (node (ref "J1") (pin "21") (pinfunction "21_21") (pintype "passive"))
      (node (ref "U1") (pin "22") (pinfunction "GPIO18/RTC_GPIO18/U1RXD/ADC2_CH7/CLK_OUT3_22") (pintype "passive"))
    )
    (net (code "41") (name "/GPIO21") (class "Default")
      (node (ref "J2") (pin "19") (pinfunction "19_19") (pintype "passive"))
      (node (ref "U1") (pin "25") (pinfunction "GPIO21/RTC_GPIO21_25") (pintype "passive"))
    )
    (net (code "42") (name "/GPIO26") (class "Default")
      (node (ref "J2") (pin "18") (pinfunction "18_18") (pintype "passive"))
      (node (ref "U1") (pin "26") (pinfunction "GPIO26/SPICS1_26") (pintype "passive"))
    )
    (net (code "43") (name "/GPIO33") (class "Default")
      (node (ref "J2") (pin "17") (pinfunction "17_17") (pintype "passive"))
      (node (ref "U1") (pin "28") (pinfunction "GPIO33/SPIIO4/FSPIHD/SUBSPIHD_28") (pintype "passive"))
    )
    (net (code "44") (name "/GPIO34") (class "Default")
      (node (ref "J2") (pin "16") (pinfunction "16_16") (pintype "passive"))
      (node (ref "U1") (pin "29") (pinfunction "GPIO34/SPIIO5/FSPICS0/SUBSPICS0_29") (pintype "passive"))
    )
    (net (code "45") (name "/GPIO35") (class "Default")
      (node (ref "J2") (pin "15") (pinfunction "15_15") (pintype "passive"))
      (node (ref "U1") (pin "31") (pinfunction "GPIO35/SPIIO6/FSPID/SUBSPID_31") (pintype "passive"))
    )
    (net (code "46") (name "/GPIO36") (class "Default")
      (node (ref "J2") (pin "14") (pinfunction "14_14") (pintype "passive"))
      (node (ref "U1") (pin "32") (pinfunction "GPIO36/SPIIO7/FSPICLK/SUBSPICLK_32") (pintype "passive"))
    )
    (net (code "47") (name "/GPIO37") (class "Default")
      (node (ref "J2") (pin "13") (pinfunction "13_13") (pintype "passive"))
      (node (ref "U1") (pin "33") (pinfunction "GPIO37/SPIDQS/FSPIQ/SUBSPIQ_33") (pintype "passive"))
    )
    (net (code "48") (name "/GPIO38") (class "Default")
      (node (ref "J2") (pin "12") (pinfunction "12_12") (pintype "passive"))
      (node (ref "U1") (pin "34") (pinfunction "GPIO38/FSPIWP/SUBSPIWP_34") (pintype "passive"))
    )
    (net (code "49") (name "/GPIO39") (class "Default")
      (node (ref "J2") (pin "11") (pinfunction "11_11") (pintype "passive"))
      (node (ref "U1") (pin "35") (pinfunction "MTCK/GPIO39/CLK_OUT3/SUBSPICS1_35") (pintype "passive"))
    )
    (net (code "50") (name "/GPIO40") (class "Default")
      (node (ref "J2") (pin "10") (pinfunction "10_10") (pintype "passive"))
      (node (ref "U1") (pin "36") (pinfunction "MTDO/GPIO40/CLK_OUT2_36") (pintype "passive"))
    )
    (net (code "51") (name "/GPIO41") (class "Default")
      (node (ref "J2") (pin "9") (pinfunction "9_9") (pintype "passive"))
      (node (ref "U1") (pin "37") (pinfunction "MTDI/GPIO41/CLK_OUT1_37") (pintype "passive"))
    )
    (net (code "52") (name "/GPIO42") (class "Default")
      (node (ref "J2") (pin "8") (pinfunction "8_8") (pintype "passive"))
      (node (ref "U1") (pin "38") (pinfunction "MTMS/GPIO42_38") (pintype "passive"))
    )
    (net (code "53") (name "/GPIO45") (class "Default")
      (node (ref "J2") (pin "5") (pinfunction "5_5") (pintype "passive"))
      (node (ref "U1") (pin "41") (pinfunction "GPIO45_41") (pintype "passive"))
    )
    (net (code "54") (name "/GPIO46") (class "Default")
      (node (ref "J2") (pin "4") (pinfunction "4_4") (pintype "passive"))
      (node (ref "U1") (pin "44") (pinfunction "GPIO46_44") (pintype "passive"))
    )
    (net (code "55") (name "/GPIO47") (class "Default")
      (node (ref "J2") (pin "23") (pinfunction "23_23") (pintype "passive"))
      (node (ref "U1") (pin "27") (pinfunction "GPIO47/SPICLK_P_DIFF/SUBSPICLK_P_DIFF_27") (pintype "passive"))
    )
    (net (code "56") (name "/GPIO48") (class "Default")
      (node (ref "J2") (pin "22") (pinfunction "22_22") (pintype "passive"))
      (node (ref "U1") (pin "30") (pinfunction "GPIO48/SPICLK_N_DIFF/SUBSPICLK_N_DIFF_30") (pintype "passive"))
    )
    (net (code "57") (name "/JUMP_GPIO0") (class "Default")
      (node (ref "J1") (pin "3") (pinfunction "3_3") (pintype "passive"))
      (node (ref "R21") (pin "1") (pinfunction "1_1") (pintype "passive"))
    )
    (net (code "58") (name "/RTS_FTDI") (class "Default")
      (node (ref "Q1") (pin "2") (pinfunction "E_2") (pintype "passive"))
      (node (ref "R18") (pin "1") (pinfunction "1_1") (pintype "passive"))
      (node (ref "U2") (pin "19") (pinfunction "~{RTS}_19") (pintype "passive"))
    )
    (net (code "59") (name "/RXD_FTDI") (class "Default")
      (node (ref "R19") (pin "2") (pinfunction "2_2") (pintype "passive"))
      (node (ref "U2") (pin "1") (pinfunction "RXD_1") (pintype "passive"))
    )
    (net (code "60") (name "/TXD_FTDI") (class "Default")
      (node (ref "R20") (pin "2") (pinfunction "2_2") (pintype "passive"))
      (node (ref "U2") (pin "17") (pinfunction "TXD_17") (pintype "passive"))
    )
    (net (code "61") (name "/U0RXD") (class "Default")
      (node (ref "J2") (pin "6") (pinfunction "6_6") (pintype "passive"))
      (node (ref "R20") (pin "1") (pinfunction "1_1") (pintype "passive"))
      (node (ref "U1") (pin "40") (pinfunction "U0RXD/GPIO44/CLK_OUT2_40") (pintype "passive"))
    )
    (net (code "62") (name "/U0TXD") (class "Default")
      (node (ref "J2") (pin "7") (pinfunction "7_7") (pintype "passive"))
      (node (ref "R19") (pin "1") (pinfunction "1_1") (pintype "passive"))
      (node (ref "U1") (pin "39") (pinfunction "U0TXD/GPIO43/CLK_OUT1_39") (pintype "passive"))
    )
    (net (code "63") (name "/VBUS_SENSE") (class "Default")
      (node (ref "R10") (pin "1") (pinfunction "1_1") (pintype "passive"))
      (node (ref "R13") (pin "1") (pinfunction "1_1") (pintype "passive"))
      (node (ref "U2") (pin "16") (pinfunction "CBUS3_16") (pintype "passive"))
    )
    (net (code "64") (name "GND") (class "Default")
      (node (ref "C1") (pin "1") (pinfunction "1_1") (pintype "passive"))
      (node (ref "C10") (pin "1") (pinfunction "1_1") (pintype "passive"))
      (node (ref "C11") (pin "1") (pinfunction "1_1") (pintype "passive"))
      (node (ref "C12") (pin "1") (pinfunction "1_1") (pintype "passive"))
      (node (ref "C13") (pin "1") (pinfunction "1_1") (pintype "passive"))
      (node (ref "C14") (pin "1") (pinfunction "1_1") (pintype "passive"))
      (node (ref "C15") (pin "1") (pinfunction "1_1") (pintype "passive"))
      (node (ref "C16") (pin "1") (pinfunction "1_1") (pintype "passive"))
      (node (ref "C17") (pin "1") (pinfunction "1_1") (pintype "passive"))
      (node (ref "C2") (pin "1") (pinfunction "1_1") (pintype "passive"))
      (node (ref "C3") (pin "1") (pinfunction "1_1") (pintype "passive"))
      (node (ref "C4") (pin "1") (pinfunction "1_1") (pintype "passive"))
      (node (ref "C5") (pin "1") (pinfunction "1_1") (pintype "passive"))
      (node (ref "C6") (pin "1") (pinfunction "1_1") (pintype "passive"))
      (node (ref "C7") (pin "1") (pinfunction "1_1") (pintype "passive"))
      (node (ref "C8") (pin "1") (pinfunction "1_1") (pintype "passive"))
      (node (ref "C9") (pin "1") (pinfunction "1_1") (pintype "passive"))
      (node (ref "D1") (pin "1") (pinfunction "1_1") (pintype "passive"))
      (node (ref "D3") (pin "1") (pinfunction "1_1") (pintype "passive"))
      (node (ref "D4") (pin "1") (pinfunction "1_1") (pintype "passive"))
      (node (ref "D5") (pin "1") (pinfunction "1_1") (pintype "passive"))
      (node (ref "D6") (pin "1") (pinfunction "1_1") (pintype "passive"))
      (node (ref "D7") (pin "1") (pinfunction "1_1") (pintype "passive"))
      (node (ref "D8") (pin "1") (pinfunction "1_1") (pintype "passive"))
      (node (ref "J1") (pin "1") (pinfunction "1_1") (pintype "passive"))
      (node (ref "J1") (pin "23") (pinfunction "23_23") (pintype "passive"))
      (node (ref "J2") (pin "2") (pinfunction "2_2") (pintype "passive"))
      (node (ref "J2") (pin "24") (pinfunction "24_24") (pintype "passive"))
      (node (ref "J3") (pin "A1B12") (pinfunction "GND_A1B12_A1B12") (pintype "passive"))
      (node (ref "J3") (pin "B1A12") (pinfunction "GND_B1A12_B1A12") (pintype "passive"))
      (node (ref "J3") (pin "S1") (pinfunction "SHIELD_1_S1") (pintype "passive"))
      (node (ref "J3") (pin "S2") (pinfunction "SHIELD_2_S2") (pintype "passive"))
      (node (ref "J3") (pin "S3") (pinfunction "SHIELD_3_S3") (pintype "passive"))
      (node (ref "J3") (pin "S4") (pinfunction "SHIELD_4_S4") (pintype "passive"))
      (node (ref "J4") (pin "A1B12") (pinfunction "GND_A1B12_A1B12") (pintype "passive"))
      (node (ref "J4") (pin "B1A12") (pinfunction "GND_B1A12_B1A12") (pintype "passive"))
      (node (ref "J4") (pin "S1") (pinfunction "SHIELD_1_S1") (pintype "passive"))
      (node (ref "J4") (pin "S2") (pinfunction "SHIELD_2_S2") (pintype "passive"))
      (node (ref "J4") (pin "S3") (pinfunction "SHIELD_3_S3") (pintype "passive"))
      (node (ref "J4") (pin "S4") (pinfunction "SHIELD_4_S4") (pintype "passive"))
      (node (ref "R11") (pin "1") (pinfunction "1_1") (pintype "passive"))
      (node (ref "R12") (pin "1") (pinfunction "1_1") (pintype "passive"))
      (node (ref "R13") (pin "2") (pinfunction "2_2") (pintype "passive"))
      (node (ref "R14") (pin "1") (pinfunction "1_1") (pintype "passive"))
      (node (ref "R15") (pin "1") (pinfunction "1_1") (pintype "passive"))
      (node (ref "R9") (pin "2") (pinfunction "2_2") (pintype "passive"))
      (node (ref "SW1") (pin "3") (pinfunction "3_3") (pintype "passive"))
      (node (ref "SW1") (pin "4") (pinfunction "4_4") (pintype "passive"))
      (node (ref "SW2") (pin "3") (pinfunction "3_3") (pintype "passive"))
      (node (ref "SW2") (pin "4") (pinfunction "4_4") (pintype "passive"))
      (node (ref "U1") (pin "1") (pinfunction "GND_01_1") (pintype "passive"))
      (node (ref "U1") (pin "2") (pinfunction "GND_02_2") (pintype "passive"))
      (node (ref "U1") (pin "42") (pinfunction "GND_42") (pintype "passive"))
      (node (ref "U1") (pin "43") (pinfunction "GND_43") (pintype "passive"))
      (node (ref "U1") (pin "46") (pinfunction "GND_46_46") (pintype "passive"))
      (node (ref "U1") (pin "47") (pinfunction "GND_47_47") (pintype "passive"))
      (node (ref "U1") (pin "48") (pinfunction "GND_48_48") (pintype "passive"))
      (node (ref "U1") (pin "49") (pinfunction "GND_49_49") (pintype "passive"))
      (node (ref "U1") (pin "50") (pinfunction "GND_50_50") (pintype "passive"))
      (node (ref "U1") (pin "51") (pinfunction "GND_51_51") (pintype "passive"))
      (node (ref "U1") (pin "52") (pinfunction "GND_52_52") (pintype "passive"))
      (node (ref "U1") (pin "53") (pinfunction "GND_53_53") (pintype "passive"))
      (node (ref "U1") (pin "54") (pinfunction "GND_54_54") (pintype "passive"))
      (node (ref "U1") (pin "55") (pinfunction "GND_55_55") (pintype "passive"))
      (node (ref "U1") (pin "56") (pinfunction "GND_56_56") (pintype "passive"))
      (node (ref "U1") (pin "57") (pinfunction "GND_57_57") (pintype "passive"))
      (node (ref "U1") (pin "58") (pinfunction "GND_58_58") (pintype "passive"))
      (node (ref "U1") (pin "59") (pinfunction "GND_59_59") (pintype "passive"))
      (node (ref "U1") (pin "60") (pinfunction "GND_60_60") (pintype "passive"))
      (node (ref "U1") (pin "61") (pinfunction "GND_61_61") (pintype "passive"))
      (node (ref "U1") (pin "62") (pinfunction "GND_62_62") (pintype "passive"))
      (node (ref "U1") (pin "63") (pinfunction "GND_63_63") (pintype "passive"))
      (node (ref "U1") (pin "64") (pinfunction "GND_64_64") (pintype "passive"))
      (node (ref "U1") (pin "65") (pinfunction "GND_65_65") (pintype "passive"))
      (node (ref "U1") (pin "66") (pinfunction "GND_66_66") (pintype "passive"))
      (node (ref "U1") (pin "67") (pinfunction "GND_67_67") (pintype "passive"))
      (node (ref "U1") (pin "68") (pinfunction "GND_68_68") (pintype "passive"))
      (node (ref "U1") (pin "69") (pinfunction "GND_69_69") (pintype "passive"))
      (node (ref "U1") (pin "70") (pinfunction "GND_70_70") (pintype "passive"))
      (node (ref "U1") (pin "71") (pinfunction "GND_71_71") (pintype "passive"))
      (node (ref "U1") (pin "72") (pinfunction "GND_72_72") (pintype "passive"))
      (node (ref "U1") (pin "73") (pinfunction "GND_73_73") (pintype "passive"))
      (node (ref "U2") (pin "13") (pinfunction "GND_13") (pintype "passive"))
      (node (ref "U2") (pin "21") (pinfunction "GND_21") (pintype "passive"))
      (node (ref "U2") (pin "3") (pinfunction "GND_3") (pintype "passive"))
      (node (ref "U3") (pin "2") (pinfunction "GND_2") (pintype "power_in"))
      (node (ref "U3") (pin "4") (pinfunction "GND_4") (pintype "power_in"))
    )
    (net (code "65") (name "Net-(D1-Pad2)") (class "Default")
      (node (ref "D1") (pin "2") (pinfunction "2_2") (pintype "passive"))
      (node (ref "R3") (pin "1") (pinfunction "1_1") (pintype "passive"))
    )
    (net (code "66") (name "Net-(D2-Pad2)") (class "Default")
      (node (ref "D2") (pin "2") (pinfunction "2_2") (pintype "passive"))
      (node (ref "R4") (pin "1") (pinfunction "1_1") (pintype "passive"))
    )
    (net (code "67") (name "Net-(J3-CC1)") (class "Default")
      (node (ref "J3") (pin "A5") (pinfunction "CC1_A5") (pintype "passive"))
      (node (ref "R12") (pin "2") (pinfunction "2_2") (pintype "passive"))
    )
    (net (code "68") (name "Net-(J3-CC2)") (class "Default")
      (node (ref "J3") (pin "B5") (pinfunction "CC2_B5") (pintype "passive"))
      (node (ref "R11") (pin "2") (pinfunction "2_2") (pintype "passive"))
    )
    (net (code "69") (name "Net-(J4-CC1)") (class "Default")
      (node (ref "J4") (pin "A5") (pinfunction "CC1_A5") (pintype "passive"))
      (node (ref "R15") (pin "2") (pinfunction "2_2") (pintype "passive"))
    )
    (net (code "70") (name "Net-(J4-CC2)") (class "Default")
      (node (ref "J4") (pin "B5") (pinfunction "CC2_B5") (pintype "passive"))
      (node (ref "R14") (pin "2") (pinfunction "2_2") (pintype "passive"))
    )
    (net (code "71") (name "Net-(Q1-B)") (class "Default")
      (node (ref "Q1") (pin "1") (pinfunction "B_1") (pintype "passive"))
      (node (ref "R16") (pin "2") (pinfunction "2_2") (pintype "passive"))
    )
    (net (code "72") (name "Net-(Q2-B)") (class "Default")
      (node (ref "Q2") (pin "1") (pinfunction "B_1") (pintype "passive"))
      (node (ref "R18") (pin "2") (pinfunction "2_2") (pintype "passive"))
    )
    (net (code "73") (name "Net-(U2-CBUS0)") (class "Default")
      (node (ref "R9") (pin "1") (pinfunction "1_1") (pintype "passive"))
      (node (ref "U2") (pin "15") (pinfunction "CBUS0_15") (pintype "passive"))
    )
    (net (code "74") (name "unconnected-(J1-Pad24)") (class "Default")
      (node (ref "J1") (pin "24") (pinfunction "24_24") (pintype "passive+no_connect"))
    )
    (net (code "75") (name "unconnected-(J3-SBU1-PadA8)") (class "Default")
      (node (ref "J3") (pin "A8") (pinfunction "SBU1_A8") (pintype "passive+no_connect"))
    )
    (net (code "76") (name "unconnected-(J3-SBU2-PadB8)") (class "Default")
      (node (ref "J3") (pin "B8") (pinfunction "SBU2_B8") (pintype "passive+no_connect"))
    )
    (net (code "77") (name "unconnected-(J4-SBU1-PadA8)") (class "Default")
      (node (ref "J4") (pin "A8") (pinfunction "SBU1_A8") (pintype "passive+no_connect"))
    )
    (net (code "78") (name "unconnected-(J4-SBU2-PadB8)") (class "Default")
      (node (ref "J4") (pin "B8") (pinfunction "SBU2_B8") (pintype "passive+no_connect"))
    )
    (net (code "79") (name "unconnected-(U2-CBUS1-Pad14)") (class "Default")
      (node (ref "U2") (pin "14") (pinfunction "CBUS1_14") (pintype "passive+no_connect"))
    )
    (net (code "80") (name "unconnected-(U2-CBUS2-Pad7)") (class "Default")
      (node (ref "U2") (pin "7") (pinfunction "CBUS2_7") (pintype "passive+no_connect"))
    )
    (net (code "81") (name "unconnected-(U2-~{CTS}-Pad6)") (class "Default")
      (node (ref "U2") (pin "6") (pinfunction "~{CTS}_6") (pintype "passive+no_connect"))
    )
    (net (code "82") (name "unconnected-(U2-~{DCD}-Pad5)") (class "Default")
      (node (ref "U2") (pin "5") (pinfunction "~{DCD}_5") (pintype "passive+no_connect"))
    )
    (net (code "83") (name "unconnected-(U2-~{DSR}-Pad4)") (class "Default")
      (node (ref "U2") (pin "4") (pinfunction "~{DSR}_4") (pintype "passive+no_connect"))
    )
    (net (code "84") (name "unconnected-(U2-~{RI}-Pad2)") (class "Default")
      (node (ref "U2") (pin "2") (pinfunction "~{RI}_2") (pintype "passive+no_connect"))
    )
  )
)
